# Connectors.net
KiCad netlist of a schematic drawn in Altium Designer
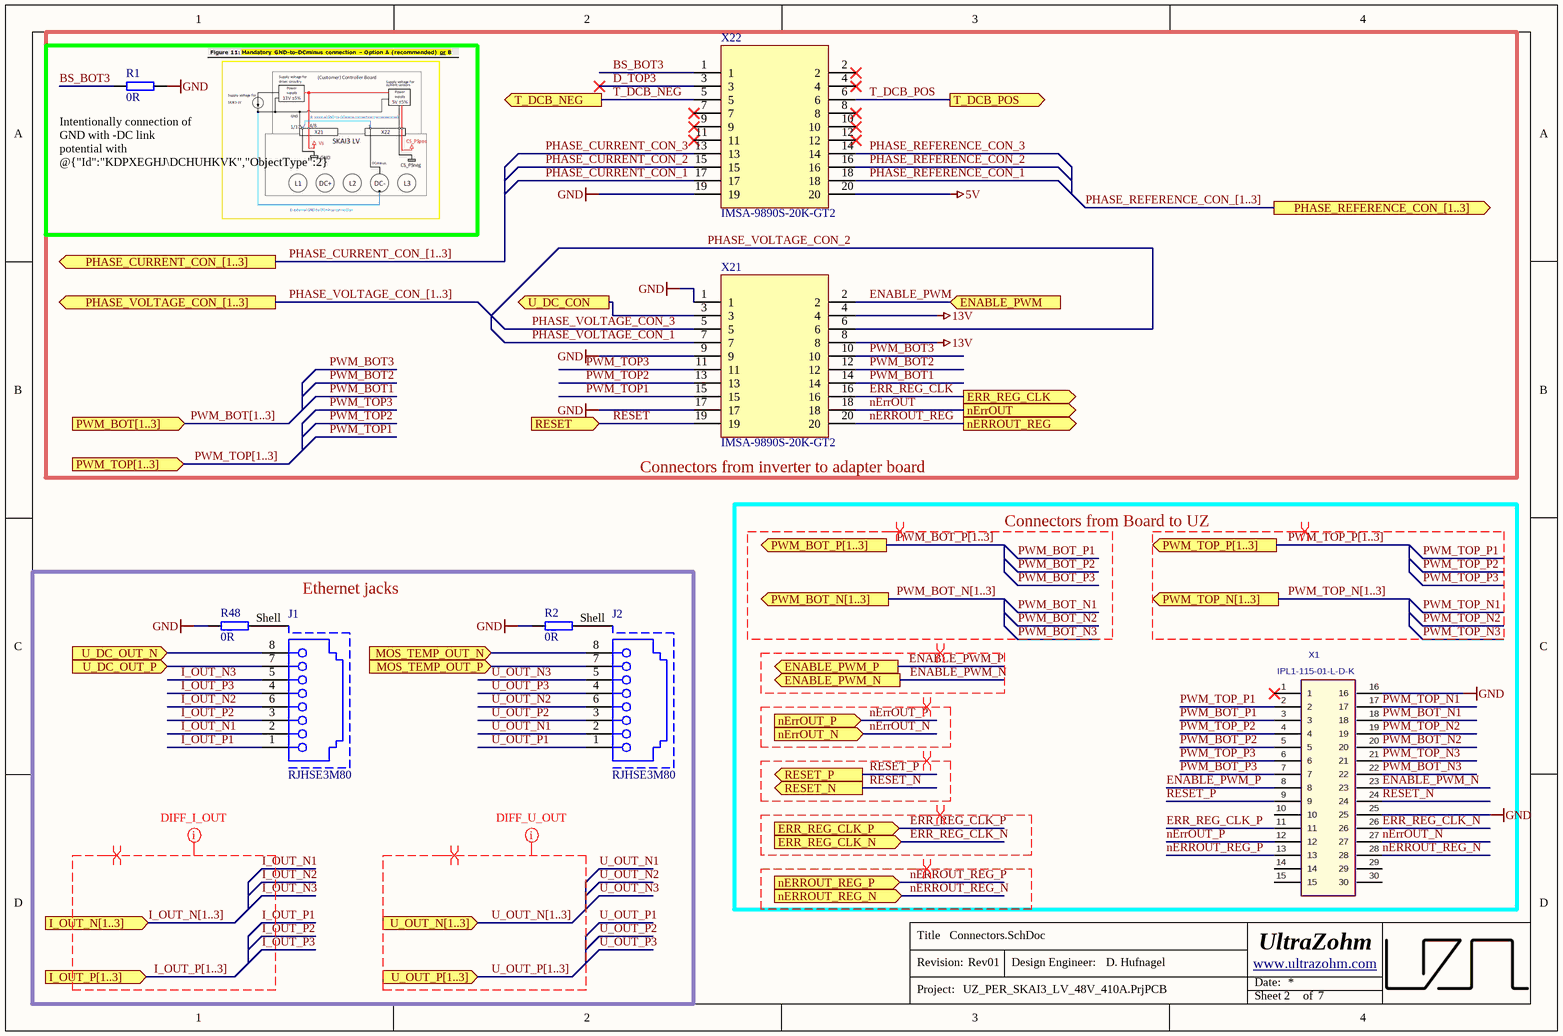
[diagram p0: Connectors.SchDoc]

(export (version "E")
  (design (tool "Eeschema 10.0.6"))
  (components
    (comp (ref "J1")
      (value "RJHSE3M80")
      (footprint "RJHSE3M80")
      (description "CAT5, RJ45 Connector, 1 port, vertical")
      (fields
        (field (name "MANUFACTURER") "Amphenol")
        (field (name "LCSC PART NUMBER") "C3179193")
        (field (name "CREATED FROM") "DHufnagel")
      )
      (libsource (lib "user") (part "RJHSE3M80"))
    )
    (comp (ref "J2")
      (value "RJHSE3M80")
      (footprint "RJHSE3M80")
      (description "CAT5, RJ45 Connector, 1 port, vertical")
      (fields
        (field (name "MANUFACTURER") "Amphenol")
        (field (name "LCSC PART NUMBER") "C3179193")
        (field (name "CREATED FROM") "DHufnagel")
      )
      (libsource (lib "user") (part "RJHSE3M80"))
    )
    (comp (ref "R1")
      (value "0R")
      (footprint "RES 0603_1608")
      (description "SMD resistor E24 series")
      (fields
        (field (name "MANUFACTURER PART NUMBER") "RC0603JR-070RL")
        (field (name "MANUFACTURER") "YAGEO")
        (field (name "CREATED FROM") "MGremer")
      )
      (libsource (lib "user") (part "Resistor"))
    )
    (comp (ref "R2")
      (value "0R")
      (footprint "RES 0603_1608")
      (description "SMD resistor E24 series")
      (fields
        (field (name "MANUFACTURER PART NUMBER") "RC0603JR-070RL")
        (field (name "MANUFACTURER") "YAGEO")
        (field (name "CREATED FROM") "MGremer")
      )
      (libsource (lib "user") (part "Resistor"))
    )
    (comp (ref "R48")
      (value "0R")
      (footprint "RES 0603_1608")
      (description "SMD resistor E24 series")
      (fields
        (field (name "MANUFACTURER PART NUMBER") "RC0603JR-070RL")
        (field (name "MANUFACTURER") "YAGEO")
        (field (name "CREATED FROM") "MGremer")
      )
      (libsource (lib "user") (part "Resistor"))
    )
    (comp (ref "X1")
      (value "IPL1-115-01-L-D-K")
      (footprint "IPL1-115-01-YYY-D-K")
      (description "2.54 mm Double Row Terminal Assembly")
      (fields (field (name "MANUFACTURER") "SAMTEC") (field (name "CREATED FROM") "MGremer"))
      (libsource (lib "user") (part "IPL1-115-01-XX-D-XX"))
    )
    (comp (ref "X21")
      (value "IMSA-9890S-20K-GT2")
      (footprint "IMSA-9890S-20Z924")
      (description "Board to Board Connector")
      (fields (field (name "MANUFACTURER") "IRISO") (field (name "CREATED FROM") "DHufnagel"))
      (libsource (lib "user") (part "IMSA-9890S-20Z924"))
    )
    (comp (ref "X22")
      (value "IMSA-9890S-20K-GT2")
      (footprint "IMSA-9890S-20Z924")
      (description "Board to Board Connector")
      (fields (field (name "MANUFACTURER") "IRISO") (field (name "CREATED FROM") "DHufnagel"))
      (libsource (lib "user") (part "IMSA-9890S-20Z924"))
    )
  )
  (nets
    (net (code "1") (name "/BS_BOT3") (class "Default")
      (node (ref "R1") (pin "1") (pinfunction "1_1") (pintype "passive"))
      (node (ref "X22") (pin "1") (pinfunction "1_1") (pintype "passive"))
    )
    (net (code "2") (name "/D_TOP3") (class "Default")
      (node (ref "X22") (pin "3") (pinfunction "3_3") (pintype "passive+no_connect"))
    )
    (net (code "3") (name "/ENABLE_PWM") (class "Default")
      (node (ref "X21") (pin "2") (pinfunction "2_2") (pintype "passive"))
    )
    (net (code "4") (name "/ENABLE_PWM_N") (class "Default")
      (node (ref "X1") (pin "23") (pinfunction "23_23") (pintype "passive"))
    )
    (net (code "5") (name "/ENABLE_PWM_P") (class "Default")
      (node (ref "X1") (pin "8") (pinfunction "8_8") (pintype "passive"))
    )
    (net (code "6") (name "/ERR_REG_CLK") (class "Default")
      (node (ref "X21") (pin "16") (pinfunction "16_16") (pintype "passive"))
    )
    (net (code "7") (name "/ERR_REG_CLK_N") (class "Default")
      (node (ref "X1") (pin "26") (pinfunction "26_26") (pintype "passive"))
    )
    (net (code "8") (name "/ERR_REG_CLK_P") (class "Default")
      (node (ref "X1") (pin "11") (pinfunction "11_11") (pintype "passive"))
    )
    (net (code "9") (name "/I_OUT_N1") (class "Default")
      (node (ref "J1") (pin "2") (pinfunction "2_2") (pintype "passive"))
    )
    (net (code "10") (name "/I_OUT_N2") (class "Default")
      (node (ref "J1") (pin "6") (pinfunction "6_6") (pintype "passive"))
    )
    (net (code "11") (name "/I_OUT_N3") (class "Default")
      (node (ref "J1") (pin "5") (pinfunction "5_5") (pintype "passive"))
    )
    (net (code "13") (name "/I_OUT_P1") (class "Default")
      (node (ref "J1") (pin "1") (pinfunction "1_1") (pintype "passive"))
    )
    (net (code "14") (name "/I_OUT_P2") (class "Default")
      (node (ref "J1") (pin "3") (pinfunction "3_3") (pintype "passive"))
    )
    (net (code "15") (name "/I_OUT_P3") (class "Default")
      (node (ref "J1") (pin "4") (pinfunction "4_4") (pintype "passive"))
    )
    (net (code "17") (name "/MOS_TEMP_OUT_N") (class "Default")
      (node (ref "J2") (pin "8") (pinfunction "8_8") (pintype "passive"))
    )
    (net (code "18") (name "/MOS_TEMP_OUT_P") (class "Default")
      (node (ref "J2") (pin "7") (pinfunction "7_7") (pintype "passive"))
    )
    (net (code "19") (name "/PHASE_CURRENT_CON_1") (class "Default")
      (node (ref "X22") (pin "17") (pinfunction "17_17") (pintype "passive"))
    )
    (net (code "20") (name "/PHASE_CURRENT_CON_2") (class "Default")
      (node (ref "X22") (pin "15") (pinfunction "15_15") (pintype "passive"))
    )
    (net (code "21") (name "/PHASE_CURRENT_CON_3") (class "Default")
      (node (ref "X22") (pin "13") (pinfunction "13_13") (pintype "passive"))
    )
    (net (code "23") (name "/PHASE_REFERENCE_CON_1") (class "Default")
      (node (ref "X22") (pin "18") (pinfunction "18_18") (pintype "passive"))
    )
    (net (code "24") (name "/PHASE_REFERENCE_CON_2") (class "Default")
      (node (ref "X22") (pin "16") (pinfunction "16_16") (pintype "passive"))
    )
    (net (code "25") (name "/PHASE_REFERENCE_CON_3") (class "Default")
      (node (ref "X22") (pin "14") (pinfunction "14_14") (pintype "passive"))
    )
    (net (code "27") (name "/PHASE_VOLTAGE_CON_1") (class "Default")
      (node (ref "X21") (pin "7") (pinfunction "7_7") (pintype "passive"))
    )
    (net (code "28") (name "/PHASE_VOLTAGE_CON_2") (class "Default")
      (node (ref "X21") (pin "6") (pinfunction "6_6") (pintype "passive"))
    )
    (net (code "29") (name "/PHASE_VOLTAGE_CON_3") (class "Default")
      (node (ref "X21") (pin "5") (pinfunction "5_5") (pintype "passive"))
    )
    (net (code "31") (name "/PWM_BOT1") (class "Default")
      (node (ref "X21") (pin "14") (pinfunction "14_14") (pintype "passive"))
    )
    (net (code "32") (name "/PWM_BOT2") (class "Default")
      (node (ref "X21") (pin "12") (pinfunction "12_12") (pintype "passive"))
    )
    (net (code "33") (name "/PWM_BOT3") (class "Default")
      (node (ref "X21") (pin "10") (pinfunction "10_10") (pintype "passive"))
    )
    (net (code "35") (name "/PWM_BOT_N1") (class "Default")
      (node (ref "X1") (pin "18") (pinfunction "18_18") (pintype "passive"))
    )
    (net (code "36") (name "/PWM_BOT_N2") (class "Default")
      (node (ref "X1") (pin "20") (pinfunction "20_20") (pintype "passive"))
    )
    (net (code "37") (name "/PWM_BOT_N3") (class "Default")
      (node (ref "X1") (pin "22") (pinfunction "22_22") (pintype "passive"))
    )
    (net (code "39") (name "/PWM_BOT_P1") (class "Default")
      (node (ref "X1") (pin "3") (pinfunction "3_3") (pintype "passive"))
    )
    (net (code "40") (name "/PWM_BOT_P2") (class "Default")
      (node (ref "X1") (pin "5") (pinfunction "5_5") (pintype "passive"))
    )
    (net (code "41") (name "/PWM_BOT_P3") (class "Default")
      (node (ref "X1") (pin "7") (pinfunction "7_7") (pintype "passive"))
    )
    (net (code "43") (name "/PWM_TOP1") (class "Default")
      (node (ref "X21") (pin "15") (pinfunction "15_15") (pintype "passive"))
    )
    (net (code "44") (name "/PWM_TOP2") (class "Default")
      (node (ref "X21") (pin "13") (pinfunction "13_13") (pintype "passive"))
    )
    (net (code "45") (name "/PWM_TOP3") (class "Default")
      (node (ref "X21") (pin "11") (pinfunction "11_11") (pintype "passive"))
    )
    (net (code "47") (name "/PWM_TOP_N1") (class "Default")
      (node (ref "X1") (pin "17") (pinfunction "17_17") (pintype "passive"))
    )
    (net (code "48") (name "/PWM_TOP_N2") (class "Default")
      (node (ref "X1") (pin "19") (pinfunction "19_19") (pintype "passive"))
    )
    (net (code "49") (name "/PWM_TOP_N3") (class "Default")
      (node (ref "X1") (pin "21") (pinfunction "21_21") (pintype "passive"))
    )
    (net (code "51") (name "/PWM_TOP_P1") (class "Default")
      (node (ref "X1") (pin "2") (pinfunction "2_2") (pintype "passive"))
    )
    (net (code "52") (name "/PWM_TOP_P2") (class "Default")
      (node (ref "X1") (pin "4") (pinfunction "4_4") (pintype "passive"))
    )
    (net (code "53") (name "/PWM_TOP_P3") (class "Default")
      (node (ref "X1") (pin "6") (pinfunction "6_6") (pintype "passive"))
    )
    (net (code "55") (name "/RESET") (class "Default")
      (node (ref "X21") (pin "19") (pinfunction "19_19") (pintype "passive"))
    )
    (net (code "56") (name "/RESET_N") (class "Default")
      (node (ref "X1") (pin "24") (pinfunction "24_24") (pintype "passive"))
    )
    (net (code "57") (name "/RESET_P") (class "Default")
      (node (ref "X1") (pin "9") (pinfunction "9_9") (pintype "passive"))
    )
    (net (code "58") (name "/T_DCB_NEG") (class "Default")
      (node (ref "X22") (pin "5") (pinfunction "5_5") (pintype "passive"))
    )
    (net (code "59") (name "/T_DCB_POS") (class "Default")
      (node (ref "X22") (pin "6") (pinfunction "6_6") (pintype "passive"))
    )
    (net (code "60") (name "/U_DC_CON") (class "Default")
      (node (ref "X21") (pin "3") (pinfunction "3_3") (pintype "passive"))
    )
    (net (code "61") (name "/U_DC_OUT_N") (class "Default")
      (node (ref "J1") (pin "8") (pinfunction "8_8") (pintype "passive"))
    )
    (net (code "62") (name "/U_DC_OUT_P") (class "Default")
      (node (ref "J1") (pin "7") (pinfunction "7_7") (pintype "passive"))
    )
    (net (code "63") (name "/U_OUT_N1") (class "Default")
      (node (ref "J2") (pin "2") (pinfunction "2_2") (pintype "passive"))
    )
    (net (code "64") (name "/U_OUT_N2") (class "Default")
      (node (ref "J2") (pin "6") (pinfunction "6_6") (pintype "passive"))
    )
    (net (code "65") (name "/U_OUT_N3") (class "Default")
      (node (ref "J2") (pin "5") (pinfunction "5_5") (pintype "passive"))
    )
    (net (code "67") (name "/U_OUT_P1") (class "Default")
      (node (ref "J2") (pin "1") (pinfunction "1_1") (pintype "passive"))
    )
    (net (code "68") (name "/U_OUT_P2") (class "Default")
      (node (ref "J2") (pin "3") (pinfunction "3_3") (pintype "passive"))
    )
    (net (code "69") (name "/U_OUT_P3") (class "Default")
      (node (ref "J2") (pin "4") (pinfunction "4_4") (pintype "passive"))
    )
    (net (code "71") (name "/nERROUT_REG") (class "Default")
      (node (ref "X21") (pin "20") (pinfunction "20_20") (pintype "passive"))
    )
    (net (code "72") (name "/nERROUT_REG_N") (class "Default")
      (node (ref "X1") (pin "28") (pinfunction "28_28") (pintype "passive"))
    )
    (net (code "73") (name "/nERROUT_REG_P") (class "Default")
      (node (ref "X1") (pin "13") (pinfunction "13_13") (pintype "passive"))
    )
    (net (code "74") (name "/nErrOUT") (class "Default")
      (node (ref "X21") (pin "18") (pinfunction "18_18") (pintype "passive"))
    )
    (net (code "75") (name "/nErrOUT_N") (class "Default")
      (node (ref "X1") (pin "27") (pinfunction "27_27") (pintype "passive"))
    )
    (net (code "76") (name "/nErrOUT_P") (class "Default")
      (node (ref "X1") (pin "12") (pinfunction "12_12") (pintype "passive"))
    )
    (net (code "77") (name "5V") (class "Default")
      (node (ref "X22") (pin "20") (pinfunction "20_20") (pintype "passive"))
    )
    (net (code "78") (name "13V") (class "Default")
      (node (ref "X21") (pin "4") (pinfunction "4_4") (pintype "passive"))
      (node (ref "X21") (pin "8") (pinfunction "8_8") (pintype "passive"))
    )
    (net (code "79") (name "GND") (class "Default")
      (node (ref "R1") (pin "2") (pinfunction "2_2") (pintype "passive"))
      (node (ref "R2") (pin "1") (pinfunction "1_1") (pintype "passive"))
      (node (ref "R48") (pin "1") (pinfunction "1_1") (pintype "passive"))
      (node (ref "X1") (pin "16") (pinfunction "16_16") (pintype "passive"))
      (node (ref "X1") (pin "25") (pinfunction "25_25") (pintype "passive"))
      (node (ref "X21") (pin "1") (pinfunction "1_1") (pintype "passive"))
      (node (ref "X21") (pin "17") (pinfunction "17_17") (pintype "passive"))
      (node (ref "X21") (pin "9") (pinfunction "9_9") (pintype "passive"))
      (node (ref "X22") (pin "19") (pinfunction "19_19") (pintype "passive"))
    )
    (net (code "80") (name "Net-(J1-PadShell)") (class "Default")
      (node (ref "J1") (pin "Shell") (pinfunction "Shell_Shell") (pintype "passive"))
      (node (ref "R48") (pin "2") (pinfunction "2_2") (pintype "passive"))
    )
    (net (code "81") (name "Net-(J2-PadShell)") (class "Default")
      (node (ref "J2") (pin "Shell") (pinfunction "Shell_Shell") (pintype "passive"))
      (node (ref "R2") (pin "2") (pinfunction "2_2") (pintype "passive"))
    )
    (net (code "82") (name "unconnected-(X1-Pad1)") (class "Default")
      (node (ref "X1") (pin "1") (pinfunction "1_1") (pintype "passive+no_connect"))
    )
    (net (code "83") (name "unconnected-(X1-Pad10)") (class "Default")
      (node (ref "X1") (pin "10") (pinfunction "10_10") (pintype "passive"))
    )
    (net (code "84") (name "unconnected-(X1-Pad14)") (class "Default")
      (node (ref "X1") (pin "14") (pinfunction "14_14") (pintype "passive"))
    )
    (net (code "85") (name "unconnected-(X1-Pad15)") (class "Default")
      (node (ref "X1") (pin "15") (pinfunction "15_15") (pintype "passive"))
    )
    (net (code "86") (name "unconnected-(X1-Pad29)") (class "Default")
      (node (ref "X1") (pin "29") (pinfunction "29_29") (pintype "passive"))
    )
    (net (code "87") (name "unconnected-(X1-Pad30)") (class "Default")
      (node (ref "X1") (pin "30") (pinfunction "30_30") (pintype "passive"))
    )
    (net (code "88") (name "unconnected-(X22-Pad2)") (class "Default")
      (node (ref "X22") (pin "2") (pinfunction "2_2") (pintype "passive+no_connect"))
    )
    (net (code "89") (name "unconnected-(X22-Pad4)") (class "Default")
      (node (ref "X22") (pin "4") (pinfunction "4_4") (pintype "passive+no_connect"))
    )
    (net (code "90") (name "unconnected-(X22-Pad7)") (class "Default")
      (node (ref "X22") (pin "7") (pinfunction "7_7") (pintype "passive+no_connect"))
    )
    (net (code "91") (name "unconnected-(X22-Pad8)") (class "Default")
      (node (ref "X22") (pin "8") (pinfunction "8_8") (pintype "passive+no_connect"))
    )
    (net (code "92") (name "unconnected-(X22-Pad9)") (class "Default")
      (node (ref "X22") (pin "9") (pinfunction "9_9") (pintype "passive+no_connect"))
    )
    (net (code "93") (name "unconnected-(X22-Pad10)") (class "Default")
      (node (ref "X22") (pin "10") (pinfunction "10_10") (pintype "passive+no_connect"))
    )
    (net (code "94") (name "unconnected-(X22-Pad11)") (class "Default")
      (node (ref "X22") (pin "11") (pinfunction "11_11") (pintype "passive+no_connect"))
    )
    (net (code "95") (name "unconnected-(X22-Pad12)") (class "Default")
      (node (ref "X22") (pin "12") (pinfunction "12_12") (pintype "passive+no_connect"))
    )
  )
)
